# stm32f103-dev-board.net
KiCad netlist of a schematic drawn in EAGLE
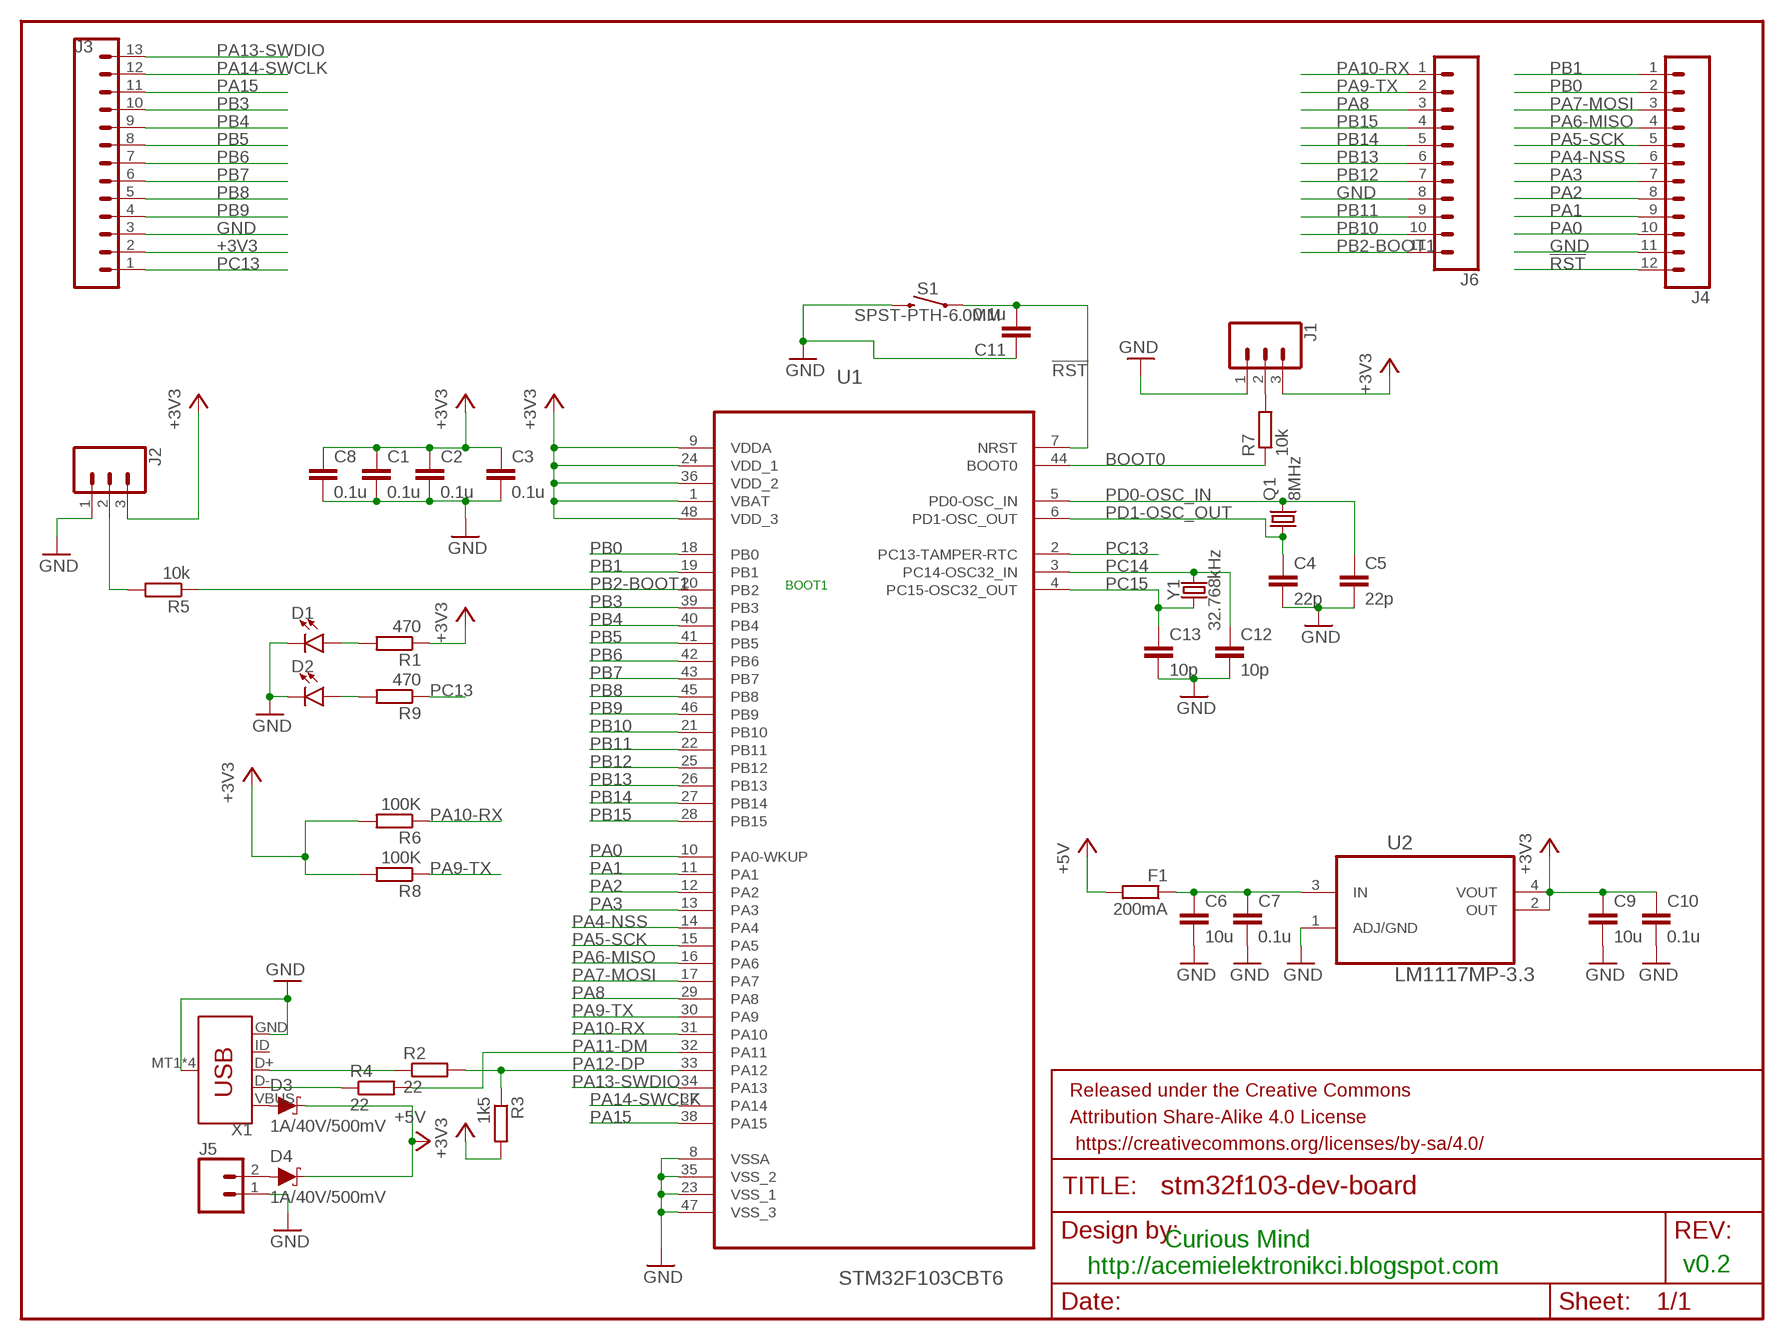
[diagram p0: schematic, sheet 1]

(export (version "E")
  (design (tool "Eeschema 10.0.6"))
  (components
    (comp (ref "C1")
      (value "0.1u")
      (footprint "eagle-import:C0805K")
      (libsource (lib "eagle-import") (part "C-EUC0805K"))
    )
    (comp (ref "C2")
      (value "0.1u")
      (footprint "eagle-import:C0805K")
      (libsource (lib "eagle-import") (part "C-EUC0805K"))
    )
    (comp (ref "C3")
      (value "0.1u")
      (footprint "eagle-import:C0805K")
      (libsource (lib "eagle-import") (part "C-EUC0805K"))
    )
    (comp (ref "C4")
      (value "22p")
      (footprint "eagle-import:C0805K")
      (libsource (lib "eagle-import") (part "C-EUC0805K"))
    )
    (comp (ref "C5")
      (value "22p")
      (footprint "eagle-import:C0805K")
      (libsource (lib "eagle-import") (part "C-EUC0805K"))
    )
    (comp (ref "C6")
      (value "10u")
      (footprint "eagle-import:C0805K")
      (libsource (lib "eagle-import") (part "C-EUC0805K"))
    )
    (comp (ref "C7")
      (value "0.1u")
      (footprint "eagle-import:C0805K")
      (libsource (lib "eagle-import") (part "C-EUC0805K"))
    )
    (comp (ref "C8")
      (value "0.1u")
      (footprint "eagle-import:C0805K")
      (libsource (lib "eagle-import") (part "C-EUC0805K"))
    )
    (comp (ref "C9")
      (value "10u")
      (footprint "eagle-import:C0805K")
      (libsource (lib "eagle-import") (part "C-EUC0805K"))
    )
    (comp (ref "C10")
      (value "0.1u")
      (footprint "eagle-import:C0805K")
      (libsource (lib "eagle-import") (part "C-EUC0805K"))
    )
    (comp (ref "C11")
      (value "0.1u")
      (footprint "eagle-import:C0805K")
      (libsource (lib "eagle-import") (part "C-EUC0805K"))
    )
    (comp (ref "C12")
      (value "10p")
      (footprint "eagle-import:C1206K")
      (libsource (lib "eagle-import") (part "C-EUC1206K"))
    )
    (comp (ref "C13")
      (value "10p")
      (footprint "eagle-import:C1206K")
      (libsource (lib "eagle-import") (part "C-EUC1206K"))
    )
    (comp (ref "D1")
      (value "LED3MM")
      (footprint "eagle-import:LED_3MM")
      (libsource (lib "eagle-import") (part "LED3MM"))
    )
    (comp (ref "D2")
      (value "LED3MM")
      (footprint "eagle-import:LED_3MM")
      (libsource (lib "eagle-import") (part "LED3MM"))
    )
    (comp (ref "D3")
      (value "1A/40V/500mV")
      (footprint "eagle-import:SMA-DIODE")
      (libsource (lib "eagle-import") (part "DIODE-SCHOTTKY-SS14"))
    )
    (comp (ref "D4")
      (value "1A/40V/500mV")
      (footprint "eagle-import:SMA-DIODE")
      (libsource (lib "eagle-import") (part "DIODE-SCHOTTKY-SS14"))
    )
    (comp (ref "F1")
      (value "200mA")
      (footprint "eagle-import:R0805")
      (libsource (lib "eagle-import") (part "R-EU_R0805"))
    )
    (comp (ref "FRAME1")
      (value "FRAME-LETTER")
      (footprint "eagle-import:CREATIVE_COMMONS")
      (libsource (lib "eagle-import") (part "FRAME-LETTER"))
    )
    (comp (ref "J1")
      (value "CONN_03")
      (footprint "eagle-import:1X03")
      (libsource (lib "eagle-import") (part "CONN_03"))
    )
    (comp (ref "J2")
      (value "CONN_03")
      (footprint "eagle-import:1X03")
      (libsource (lib "eagle-import") (part "CONN_03"))
    )
    (comp (ref "J3")
      (value "CONN_13")
      (footprint "eagle-import:1X13")
      (libsource (lib "eagle-import") (part "CONN_13"))
    )
    (comp (ref "J4")
      (value "CONN_12")
      (footprint "eagle-import:1X12")
      (libsource (lib "eagle-import") (part "CONN_12"))
    )
    (comp (ref "J5")
      (value "CONN_02")
      (footprint "eagle-import:1X02")
      (libsource (lib "eagle-import") (part "CONN_02"))
    )
    (comp (ref "J6")
      (value "CONN_11")
      (footprint "eagle-import:1X11")
      (libsource (lib "eagle-import") (part "CONN_11"))
    )
    (comp (ref "Q1")
      (value "8MHz")
      (footprint "eagle-import:HC49_S")
      (libsource (lib "eagle-import") (part "CRYSTALHC49S"))
    )
    (comp (ref "R1")
      (value "470")
      (footprint "eagle-import:R0805")
      (libsource (lib "eagle-import") (part "R-EU_R0805"))
    )
    (comp (ref "R2")
      (value "22")
      (footprint "eagle-import:R0805")
      (libsource (lib "eagle-import") (part "R-EU_R0805"))
    )
    (comp (ref "R3")
      (value "1k5")
      (footprint "eagle-import:R1206")
      (libsource (lib "eagle-import") (part "R-EU_R1206"))
    )
    (comp (ref "R4")
      (value "22")
      (footprint "eagle-import:R0805")
      (libsource (lib "eagle-import") (part "R-EU_R0805"))
    )
    (comp (ref "R5")
      (value "10k")
      (footprint "eagle-import:R0805")
      (libsource (lib "eagle-import") (part "R-EU_R0805"))
    )
    (comp (ref "R6")
      (value "100K")
      (footprint "eagle-import:R0805")
      (libsource (lib "eagle-import") (part "R-EU_R0805"))
    )
    (comp (ref "R7")
      (value "10k")
      (footprint "eagle-import:R0805")
      (libsource (lib "eagle-import") (part "R-EU_R0805"))
    )
    (comp (ref "R8")
      (value "100K")
      (footprint "eagle-import:R0805")
      (libsource (lib "eagle-import") (part "R-EU_R0805"))
    )
    (comp (ref "R9")
      (value "470")
      (footprint "eagle-import:R0805")
      (libsource (lib "eagle-import") (part "R-EU_R0805"))
    )
    (comp (ref "S1")
      (value "SPST-PTH-6.0MM")
      (footprint "eagle-import:TACTILE_SWITCH_PTH_6.0MM")
      (libsource (lib "eagle-import") (part "MOMENTARY-SWITCH-SPST-PTH-6.0MM"))
    )
    (comp (ref "U1")
      (value "STM32F103CBT6")
      (footprint "eagle-import:QFP50P900X900X160-48N")
      (libsource (lib "eagle-import") (part "STM32F103CBT6"))
    )
    (comp (ref "U2")
      (value "LM1117MP-3.3")
      (footprint "eagle-import:SOT230P696X180-4N")
      (libsource (lib "eagle-import") (part "LM1117MP-3.3"))
    )
    (comp (ref "X1")
      (value "USB_MICRO-B_SMT")
      (footprint "eagle-import:USB-MICROB")
      (libsource (lib "eagle-import") (part "USB_MICRO-B_SMT"))
    )
    (comp (ref "Y1")
      (value "32.768kHz")
      (footprint "eagle-import:CRYSTAL-SMD-2X6-CYL")
      (libsource (lib "eagle-import") (part "CRYSTAL-32.768KHZSMD-2X6"))
    )
  )
  (nets
    (net (code "1") (name "+3V3") (class "Default")
      (node (ref "C1") (pin "1") (pinfunction "1_1") (pintype "passive"))
      (node (ref "C10") (pin "1") (pinfunction "1_1") (pintype "passive"))
      (node (ref "C2") (pin "1") (pinfunction "1_1") (pintype "passive"))
      (node (ref "C3") (pin "1") (pinfunction "1_1") (pintype "passive"))
      (node (ref "C8") (pin "1") (pinfunction "1_1") (pintype "passive"))
      (node (ref "C9") (pin "1") (pinfunction "1_1") (pintype "passive"))
      (node (ref "J1") (pin "3") (pinfunction "3_3") (pintype "passive"))
      (node (ref "J2") (pin "3") (pinfunction "3_3") (pintype "passive"))
      (node (ref "J3") (pin "2") (pinfunction "2_2") (pintype "passive"))
      (node (ref "R1") (pin "1") (pinfunction "1_1") (pintype "passive"))
      (node (ref "R3") (pin "2") (pinfunction "2_2") (pintype "passive"))
      (node (ref "R6") (pin "2") (pinfunction "2_2") (pintype "passive"))
      (node (ref "R8") (pin "2") (pinfunction "2_2") (pintype "passive"))
      (node (ref "U1") (pin "1") (pinfunction "VBAT_1") (pintype "input"))
      (node (ref "U1") (pin "24") (pinfunction "VDD_1_24") (pintype "bidirectional"))
      (node (ref "U1") (pin "36") (pinfunction "VDD_2_36") (pintype "power_in"))
      (node (ref "U1") (pin "48") (pinfunction "VDD_3_48") (pintype "power_in"))
      (node (ref "U1") (pin "9") (pinfunction "VDDA_9") (pintype "power_in"))
      (node (ref "U2") (pin "2") (pinfunction "OUT_2") (pintype "output"))
      (node (ref "U2") (pin "4") (pinfunction "VOUT_4") (pintype "output"))
    )
    (net (code "2") (name "+5V") (class "Default")
      (node (ref "D3") (pin "C") (pinfunction "C_C") (pintype "passive"))
      (node (ref "D4") (pin "C") (pinfunction "C_C") (pintype "passive"))
      (node (ref "F1") (pin "2") (pinfunction "2_2") (pintype "passive"))
    )
    (net (code "3") (name "/BOOT0") (class "Default")
      (node (ref "R7") (pin "1") (pinfunction "1_1") (pintype "passive"))
      (node (ref "U1") (pin "44") (pinfunction "BOOT0_44") (pintype "bidirectional"))
    )
    (net (code "4") (name "/PA0") (class "Default")
      (node (ref "J4") (pin "10") (pinfunction "10_10") (pintype "passive"))
      (node (ref "U1") (pin "10") (pinfunction "PA0-WKUP_10") (pintype "bidirectional"))
    )
    (net (code "5") (name "/PA1") (class "Default")
      (node (ref "J4") (pin "9") (pinfunction "9_9") (pintype "passive"))
      (node (ref "U1") (pin "11") (pinfunction "PA1_11") (pintype "bidirectional"))
    )
    (net (code "6") (name "/PA2") (class "Default")
      (node (ref "J4") (pin "8") (pinfunction "8_8") (pintype "passive"))
      (node (ref "U1") (pin "12") (pinfunction "PA2_12") (pintype "bidirectional"))
    )
    (net (code "7") (name "/PA3") (class "Default")
      (node (ref "J4") (pin "7") (pinfunction "7_7") (pintype "passive"))
      (node (ref "U1") (pin "13") (pinfunction "PA3_13") (pintype "bidirectional"))
    )
    (net (code "8") (name "/PA4-NSS") (class "Default")
      (node (ref "J4") (pin "6") (pinfunction "6_6") (pintype "passive"))
      (node (ref "U1") (pin "14") (pinfunction "PA4_14") (pintype "bidirectional"))
    )
    (net (code "9") (name "/PA5-SCK") (class "Default")
      (node (ref "J4") (pin "5") (pinfunction "5_5") (pintype "passive"))
      (node (ref "U1") (pin "15") (pinfunction "PA5_15") (pintype "bidirectional"))
    )
    (net (code "10") (name "/PA6-MISO") (class "Default")
      (node (ref "J4") (pin "4") (pinfunction "4_4") (pintype "passive"))
      (node (ref "U1") (pin "16") (pinfunction "PA6_16") (pintype "bidirectional"))
    )
    (net (code "11") (name "/PA7-MOSI") (class "Default")
      (node (ref "J4") (pin "3") (pinfunction "3_3") (pintype "passive"))
      (node (ref "U1") (pin "17") (pinfunction "PA7_17") (pintype "bidirectional"))
    )
    (net (code "12") (name "/PA8") (class "Default")
      (node (ref "J6") (pin "3") (pinfunction "3_3") (pintype "passive"))
      (node (ref "U1") (pin "29") (pinfunction "PA8_29") (pintype "bidirectional"))
    )
    (net (code "13") (name "/PA9-TX") (class "Default")
      (node (ref "J6") (pin "2") (pinfunction "2_2") (pintype "passive"))
      (node (ref "R8") (pin "1") (pinfunction "1_1") (pintype "passive"))
      (node (ref "U1") (pin "30") (pinfunction "PA9_30") (pintype "bidirectional"))
    )
    (net (code "14") (name "/PA10-RX") (class "Default")
      (node (ref "J6") (pin "1") (pinfunction "1_1") (pintype "passive"))
      (node (ref "R6") (pin "1") (pinfunction "1_1") (pintype "passive"))
      (node (ref "U1") (pin "31") (pinfunction "PA10_31") (pintype "bidirectional"))
    )
    (net (code "15") (name "/PA11-DM") (class "Default")
      (node (ref "R4") (pin "2") (pinfunction "2_2") (pintype "passive"))
      (node (ref "U1") (pin "32") (pinfunction "PA11_32") (pintype "power_in"))
    )
    (net (code "16") (name "/PA12-DP") (class "Default")
      (node (ref "R2") (pin "2") (pinfunction "2_2") (pintype "passive"))
      (node (ref "R3") (pin "1") (pinfunction "1_1") (pintype "passive"))
      (node (ref "U1") (pin "33") (pinfunction "PA12_33") (pintype "bidirectional"))
    )
    (net (code "17") (name "/PA13-SWDIO") (class "Default")
      (node (ref "J3") (pin "13") (pinfunction "13_13") (pintype "passive"))
      (node (ref "U1") (pin "34") (pinfunction "PA13_34") (pintype "bidirectional"))
    )
    (net (code "18") (name "/PA14-SWCLK") (class "Default")
      (node (ref "J3") (pin "12") (pinfunction "12_12") (pintype "passive"))
      (node (ref "U1") (pin "37") (pinfunction "PA14_37") (pintype "bidirectional"))
    )
    (net (code "19") (name "/PA15") (class "Default")
      (node (ref "J3") (pin "11") (pinfunction "11_11") (pintype "passive"))
      (node (ref "U1") (pin "38") (pinfunction "PA15_38") (pintype "bidirectional"))
    )
    (net (code "20") (name "/PB0") (class "Default")
      (node (ref "J4") (pin "2") (pinfunction "2_2") (pintype "passive"))
      (node (ref "U1") (pin "18") (pinfunction "PB0_18") (pintype "bidirectional"))
    )
    (net (code "21") (name "/PB1") (class "Default")
      (node (ref "J4") (pin "1") (pinfunction "1_1") (pintype "passive"))
      (node (ref "U1") (pin "19") (pinfunction "PB1_19") (pintype "bidirectional"))
    )
    (net (code "22") (name "/PB2-BOOT1") (class "Default")
      (node (ref "J6") (pin "11") (pinfunction "11_11") (pintype "passive"))
      (node (ref "R5") (pin "1") (pinfunction "1_1") (pintype "passive"))
      (node (ref "U1") (pin "20") (pinfunction "PB2_20") (pintype "bidirectional"))
    )
    (net (code "23") (name "/PB3") (class "Default")
      (node (ref "J3") (pin "10") (pinfunction "10_10") (pintype "passive"))
      (node (ref "U1") (pin "39") (pinfunction "PB3_39") (pintype "bidirectional"))
    )
    (net (code "24") (name "/PB4") (class "Default")
      (node (ref "J3") (pin "9") (pinfunction "9_9") (pintype "passive"))
      (node (ref "U1") (pin "40") (pinfunction "PB4_40") (pintype "bidirectional"))
    )
    (net (code "25") (name "/PB5") (class "Default")
      (node (ref "J3") (pin "8") (pinfunction "8_8") (pintype "passive"))
      (node (ref "U1") (pin "41") (pinfunction "PB5_41") (pintype "bidirectional"))
    )
    (net (code "26") (name "/PB6") (class "Default")
      (node (ref "J3") (pin "7") (pinfunction "7_7") (pintype "passive"))
      (node (ref "U1") (pin "42") (pinfunction "PB6_42") (pintype "bidirectional"))
    )
    (net (code "27") (name "/PB7") (class "Default")
      (node (ref "J3") (pin "6") (pinfunction "6_6") (pintype "passive"))
      (node (ref "U1") (pin "43") (pinfunction "PB7_43") (pintype "bidirectional"))
    )
    (net (code "28") (name "/PB8") (class "Default")
      (node (ref "J3") (pin "5") (pinfunction "5_5") (pintype "passive"))
      (node (ref "U1") (pin "45") (pinfunction "PB8_45") (pintype "bidirectional"))
    )
    (net (code "29") (name "/PB9") (class "Default")
      (node (ref "J3") (pin "4") (pinfunction "4_4") (pintype "passive"))
      (node (ref "U1") (pin "46") (pinfunction "PB9_46") (pintype "bidirectional"))
    )
    (net (code "30") (name "/PB10") (class "Default")
      (node (ref "J6") (pin "10") (pinfunction "10_10") (pintype "passive"))
      (node (ref "U1") (pin "21") (pinfunction "PB10_21") (pintype "bidirectional"))
    )
    (net (code "31") (name "/PB11") (class "Default")
      (node (ref "J6") (pin "9") (pinfunction "9_9") (pintype "passive"))
      (node (ref "U1") (pin "22") (pinfunction "PB11_22") (pintype "bidirectional"))
    )
    (net (code "32") (name "/PB12") (class "Default")
      (node (ref "J6") (pin "7") (pinfunction "7_7") (pintype "passive"))
      (node (ref "U1") (pin "25") (pinfunction "PB12_25") (pintype "bidirectional"))
    )
    (net (code "33") (name "/PB13") (class "Default")
      (node (ref "J6") (pin "6") (pinfunction "6_6") (pintype "passive"))
      (node (ref "U1") (pin "26") (pinfunction "PB13_26") (pintype "bidirectional"))
    )
    (net (code "34") (name "/PB14") (class "Default")
      (node (ref "J6") (pin "5") (pinfunction "5_5") (pintype "passive"))
      (node (ref "U1") (pin "27") (pinfunction "PB14_27") (pintype "bidirectional"))
    )
    (net (code "35") (name "/PB15") (class "Default")
      (node (ref "J6") (pin "4") (pinfunction "4_4") (pintype "passive"))
      (node (ref "U1") (pin "28") (pinfunction "PB15_28") (pintype "bidirectional"))
    )
    (net (code "36") (name "/PC13") (class "Default")
      (node (ref "J3") (pin "1") (pinfunction "1_1") (pintype "passive"))
      (node (ref "R9") (pin "1") (pinfunction "1_1") (pintype "passive"))
      (node (ref "U1") (pin "2") (pinfunction "PC13-TAMPER-RTC_2") (pintype "bidirectional"))
    )
    (net (code "37") (name "/PC14") (class "Default")
      (node (ref "C12") (pin "1") (pinfunction "1_1") (pintype "passive"))
      (node (ref "U1") (pin "3") (pinfunction "PC14-OSC32_IN_3") (pintype "bidirectional"))
      (node (ref "Y1") (pin "X2") (pinfunction "2_X2") (pintype "passive"))
    )
    (net (code "38") (name "/PC15") (class "Default")
      (node (ref "C13") (pin "1") (pinfunction "1_1") (pintype "passive"))
      (node (ref "U1") (pin "4") (pinfunction "PC15-OSC32_OUT_4") (pintype "bidirectional"))
      (node (ref "Y1") (pin "X1") (pinfunction "1_X1") (pintype "passive"))
    )
    (net (code "39") (name "/PD0-OSC_IN") (class "Default")
      (node (ref "C5") (pin "1") (pinfunction "1_1") (pintype "passive"))
      (node (ref "Q1") (pin "2") (pinfunction "2_2") (pintype "passive"))
      (node (ref "U1") (pin "5") (pinfunction "PD0-OSC_IN_5") (pintype "bidirectional"))
    )
    (net (code "40") (name "/PD1-OSC_OUT") (class "Default")
      (node (ref "C4") (pin "1") (pinfunction "1_1") (pintype "passive"))
      (node (ref "Q1") (pin "1") (pinfunction "1_1") (pintype "passive"))
      (node (ref "U1") (pin "6") (pinfunction "PD1-OSC_OUT_6") (pintype "bidirectional"))
    )
    (net (code "41") (name "/~{RST}") (class "Default")
      (node (ref "C11") (pin "2") (pinfunction "2_2") (pintype "passive"))
      (node (ref "J4") (pin "12") (pinfunction "12_12") (pintype "passive"))
      (node (ref "S1") (pin "1") (pinfunction "1_1") (pintype "passive"))
      (node (ref "U1") (pin "7") (pinfunction "NRST_7") (pintype "bidirectional"))
    )
    (net (code "42") (name "GND") (class "Default")
      (node (ref "C1") (pin "2") (pinfunction "2_2") (pintype "passive"))
      (node (ref "C10") (pin "2") (pinfunction "2_2") (pintype "passive"))
      (node (ref "C11") (pin "1") (pinfunction "1_1") (pintype "passive"))
      (node (ref "C12") (pin "2") (pinfunction "2_2") (pintype "passive"))
      (node (ref "C13") (pin "2") (pinfunction "2_2") (pintype "passive"))
      (node (ref "C2") (pin "2") (pinfunction "2_2") (pintype "passive"))
      (node (ref "C3") (pin "2") (pinfunction "2_2") (pintype "passive"))
      (node (ref "C4") (pin "2") (pinfunction "2_2") (pintype "passive"))
      (node (ref "C5") (pin "2") (pinfunction "2_2") (pintype "passive"))
      (node (ref "C6") (pin "2") (pinfunction "2_2") (pintype "passive"))
      (node (ref "C7") (pin "2") (pinfunction "2_2") (pintype "passive"))
      (node (ref "C8") (pin "2") (pinfunction "2_2") (pintype "passive"))
      (node (ref "C9") (pin "2") (pinfunction "2_2") (pintype "passive"))
      (node (ref "D1") (pin "K") (pinfunction "C_K") (pintype "passive"))
      (node (ref "D2") (pin "K") (pinfunction "C_K") (pintype "passive"))
      (node (ref "J1") (pin "1") (pinfunction "1_1") (pintype "passive"))
      (node (ref "J2") (pin "1") (pinfunction "1_1") (pintype "passive"))
      (node (ref "J3") (pin "3") (pinfunction "3_3") (pintype "passive"))
      (node (ref "J4") (pin "11") (pinfunction "11_11") (pintype "passive"))
      (node (ref "J5") (pin "1") (pinfunction "1_1") (pintype "passive"))
      (node (ref "J6") (pin "8") (pinfunction "8_8") (pintype "passive"))
      (node (ref "S1") (pin "3") (pinfunction "2_3") (pintype "passive"))
      (node (ref "U1") (pin "23") (pinfunction "VSS_1_23") (pintype "bidirectional"))
      (node (ref "U1") (pin "35") (pinfunction "VSS_2_35") (pintype "passive"))
      (node (ref "U1") (pin "47") (pinfunction "VSS_3_47") (pintype "passive"))
      (node (ref "U1") (pin "8") (pinfunction "VSSA_8") (pintype "passive"))
      (node (ref "U2") (pin "1") (pinfunction "ADJ/GND_1") (pintype "passive"))
      (node (ref "X1") (pin "GND") (pinfunction "GND_GND") (pintype "power_in"))
      (node (ref "X1") (pin "MT1") (pinfunction "SHIELD_MT1") (pintype "bidirectional"))
      (node (ref "X1") (pin "MT2") (pinfunction "SHIELD_MT2") (pintype "bidirectional"))
      (node (ref "X1") (pin "P$1") (pinfunction "SHIELD_P$1") (pintype "bidirectional"))
      (node (ref "X1") (pin "P$2") (pinfunction "SHIELD_P$2") (pintype "bidirectional"))
    )
    (net (code "43") (name "Net-(D1-PadA)") (class "Default")
      (node (ref "D1") (pin "A") (pinfunction "A_A") (pintype "passive"))
      (node (ref "R1") (pin "2") (pinfunction "2_2") (pintype "passive"))
    )
    (net (code "44") (name "Net-(D2-PadA)") (class "Default")
      (node (ref "D2") (pin "A") (pinfunction "A_A") (pintype "passive"))
      (node (ref "R9") (pin "2") (pinfunction "2_2") (pintype "passive"))
    )
    (net (code "45") (name "Net-(D3-PadA)") (class "Default")
      (node (ref "D3") (pin "A") (pinfunction "A_A") (pintype "passive"))
      (node (ref "X1") (pin "VBUS") (pinfunction "VBUS_VBUS") (pintype "power_in"))
    )
    (net (code "46") (name "Net-(D4-PadA)") (class "Default")
      (node (ref "D4") (pin "A") (pinfunction "A_A") (pintype "passive"))
      (node (ref "J5") (pin "2") (pinfunction "2_2") (pintype "passive"))
    )
    (net (code "47") (name "Net-(J1-Pad2)") (class "Default")
      (node (ref "J1") (pin "2") (pinfunction "2_2") (pintype "passive"))
      (node (ref "R7") (pin "2") (pinfunction "2_2") (pintype "passive"))
    )
    (net (code "48") (name "Net-(J2-Pad2)") (class "Default")
      (node (ref "J2") (pin "2") (pinfunction "2_2") (pintype "passive"))
      (node (ref "R5") (pin "2") (pinfunction "2_2") (pintype "passive"))
    )
    (net (code "49") (name "Net-(R2-Pad1)") (class "Default")
      (node (ref "R2") (pin "1") (pinfunction "1_1") (pintype "passive"))
      (node (ref "X1") (pin "D+") (pinfunction "D+_D+") (pintype "bidirectional"))
    )
    (net (code "50") (name "Net-(R4-Pad1)") (class "Default")
      (node (ref "R4") (pin "1") (pinfunction "1_1") (pintype "passive"))
      (node (ref "X1") (pin "D-") (pinfunction "D-_D-") (pintype "bidirectional"))
    )
    (net (code "51") (name "Net-(U2-IN)") (class "Default")
      (node (ref "C6") (pin "1") (pinfunction "1_1") (pintype "passive"))
      (node (ref "C7") (pin "1") (pinfunction "1_1") (pintype "passive"))
      (node (ref "F1") (pin "1") (pinfunction "1_1") (pintype "passive"))
      (node (ref "U2") (pin "3") (pinfunction "IN_3") (pintype "input"))
    )
    (net (code "52") (name "unconnected-(X1-PadID)") (class "Default")
      (node (ref "X1") (pin "ID") (pinfunction "ID_ID") (pintype "bidirectional"))
    )
  )
)
